# nxtMini.net
KiCad netlist of a schematic drawn in EAGLE
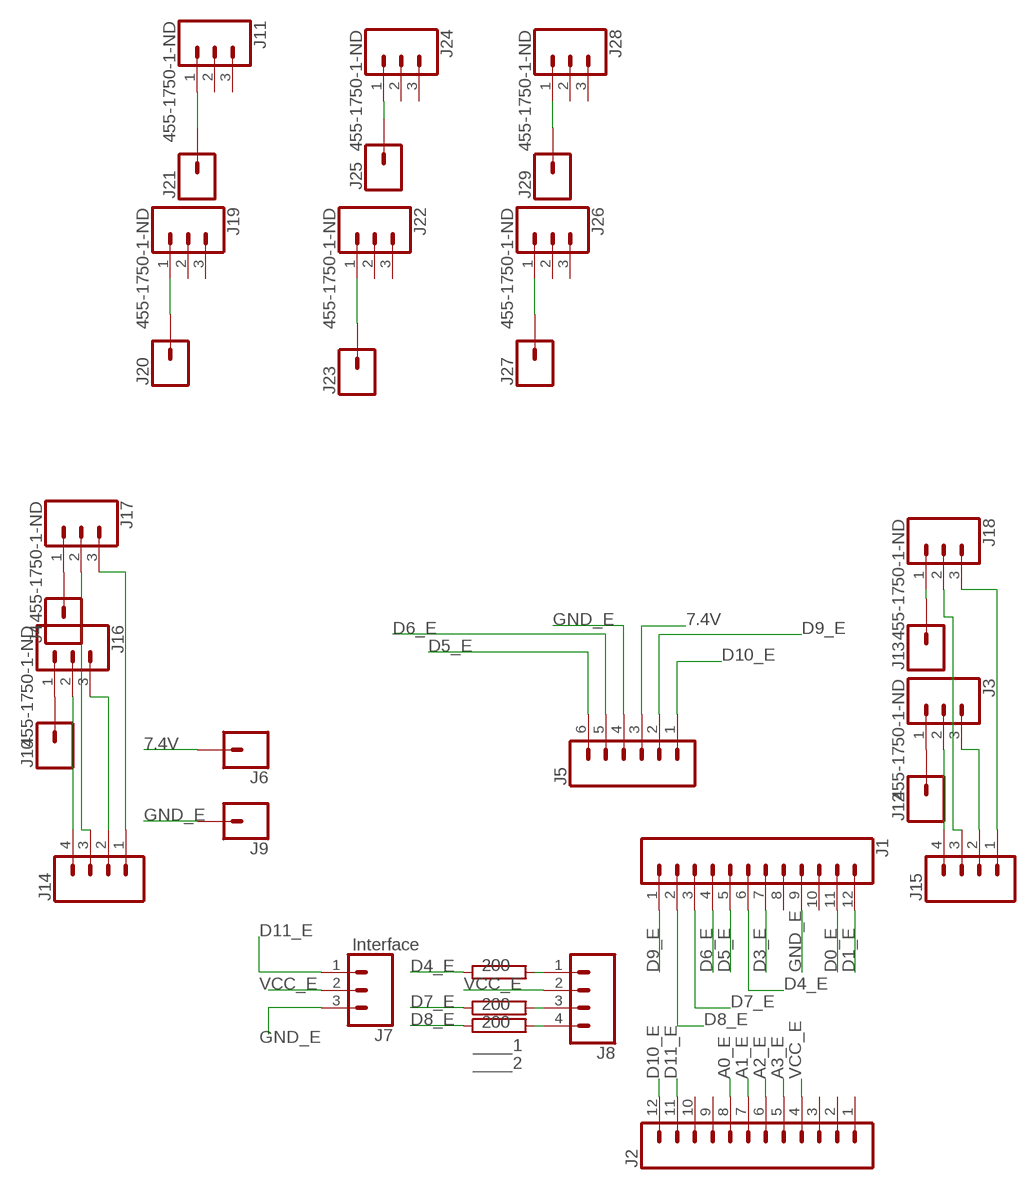
[diagram p0: schematic, sheet 1]

(export (version "E")
  (design (tool "Eeschema 10.0.6"))
  (components
    (comp (ref "200")
      (value "RCA0001")
      (footprint "eagle-import:CA0001")
      (libsource (lib "eagle-import") (part "RCA0001"))
    )
    (comp (ref "J1")
      (value "CONN_12")
      (footprint "eagle-import:1X12")
      (libsource (lib "eagle-import") (part "CONN_12"))
    )
    (comp (ref "J2")
      (value "CONN_12")
      (footprint "eagle-import:1X12")
      (libsource (lib "eagle-import") (part "CONN_12"))
    )
    (comp (ref "J3")
      (value "455-1750-1-ND")
      (footprint "eagle-import:1X03")
      (libsource (lib "eagle-import") (part "CONN_03"))
    )
    (comp (ref "J4")
      (value "CONN_01")
      (footprint "eagle-import:1X01")
      (libsource (lib "eagle-import") (part "CONN_01"))
    )
    (comp (ref "J5")
      (value "CONN_06SILK_FEMALE_PTH")
      (footprint "eagle-import:1X06")
      (libsource (lib "eagle-import") (part "CONN_06SILK_FEMALE_PTH"))
    )
    (comp (ref "J6")
      (value "CONN_01")
      (footprint "eagle-import:1X01")
      (libsource (lib "eagle-import") (part "CONN_01"))
    )
    (comp (ref "J7")
      (value "Interface")
      (footprint "eagle-import:1X03")
      (libsource (lib "eagle-import") (part "CONN_03"))
    )
    (comp (ref "J8")
      (value "CONN_04")
      (footprint "eagle-import:1X04")
      (libsource (lib "eagle-import") (part "CONN_04"))
    )
    (comp (ref "J9")
      (value "CONN_01")
      (footprint "eagle-import:1X01")
      (libsource (lib "eagle-import") (part "CONN_01"))
    )
    (comp (ref "J10")
      (value "CONN_01")
      (footprint "eagle-import:1X01")
      (libsource (lib "eagle-import") (part "CONN_01"))
    )
    (comp (ref "J11")
      (value "455-1750-1-ND")
      (footprint "eagle-import:1X03")
      (libsource (lib "eagle-import") (part "CONN_03"))
    )
    (comp (ref "J12")
      (value "CONN_01")
      (footprint "eagle-import:1X01")
      (libsource (lib "eagle-import") (part "CONN_01"))
    )
    (comp (ref "J13")
      (value "CONN_01")
      (footprint "eagle-import:1X01")
      (libsource (lib "eagle-import") (part "CONN_01"))
    )
    (comp (ref "J14")
      (value "CONN_04")
      (footprint "eagle-import:1X04")
      (libsource (lib "eagle-import") (part "CONN_04"))
    )
    (comp (ref "J15")
      (value "CONN_04")
      (footprint "eagle-import:1X04")
      (libsource (lib "eagle-import") (part "CONN_04"))
    )
    (comp (ref "J16")
      (value "455-1750-1-ND")
      (footprint "eagle-import:1X03")
      (libsource (lib "eagle-import") (part "CONN_03"))
    )
    (comp (ref "J17")
      (value "455-1750-1-ND")
      (footprint "eagle-import:1X03")
      (libsource (lib "eagle-import") (part "CONN_03"))
    )
    (comp (ref "J18")
      (value "455-1750-1-ND")
      (footprint "eagle-import:1X03")
      (libsource (lib "eagle-import") (part "CONN_03"))
    )
    (comp (ref "J19")
      (value "455-1750-1-ND")
      (footprint "eagle-import:1X03")
      (libsource (lib "eagle-import") (part "CONN_03"))
    )
    (comp (ref "J20")
      (value "CONN_01")
      (footprint "eagle-import:1X01")
      (libsource (lib "eagle-import") (part "CONN_01"))
    )
    (comp (ref "J21")
      (value "CONN_01")
      (footprint "eagle-import:1X01")
      (libsource (lib "eagle-import") (part "CONN_01"))
    )
    (comp (ref "J22")
      (value "455-1750-1-ND")
      (footprint "eagle-import:1X03")
      (libsource (lib "eagle-import") (part "CONN_03"))
    )
    (comp (ref "J23")
      (value "CONN_01")
      (footprint "eagle-import:1X01")
      (libsource (lib "eagle-import") (part "CONN_01"))
    )
    (comp (ref "J24")
      (value "455-1750-1-ND")
      (footprint "eagle-import:1X03")
      (libsource (lib "eagle-import") (part "CONN_03"))
    )
    (comp (ref "J25")
      (value "CONN_01")
      (footprint "eagle-import:1X01")
      (libsource (lib "eagle-import") (part "CONN_01"))
    )
    (comp (ref "J26")
      (value "455-1750-1-ND")
      (footprint "eagle-import:1X03")
      (libsource (lib "eagle-import") (part "CONN_03"))
    )
    (comp (ref "J27")
      (value "CONN_01")
      (footprint "eagle-import:1X01")
      (libsource (lib "eagle-import") (part "CONN_01"))
    )
    (comp (ref "J28")
      (value "455-1750-1-ND")
      (footprint "eagle-import:1X03")
      (libsource (lib "eagle-import") (part "CONN_03"))
    )
    (comp (ref "J29")
      (value "CONN_01")
      (footprint "eagle-import:1X01")
      (libsource (lib "eagle-import") (part "CONN_01"))
    )
    (comp (ref "____1")
      (value "200")
      (footprint "eagle-import:CA0001")
      (libsource (lib "eagle-import") (part "RCA0001"))
    )
    (comp (ref "____2")
      (value "200")
      (footprint "eagle-import:CA0001")
      (libsource (lib "eagle-import") (part "RCA0001"))
    )
  )
  (nets
    (net (code "1") (name "/7.4V") (class "Default")
      (node (ref "J5") (pin "3") (pinfunction "3_3") (pintype "passive"))
      (node (ref "J6") (pin "1") (pinfunction "1_1") (pintype "passive"))
    )
    (net (code "2") (name "/A0_E") (class "Default")
      (node (ref "J2") (pin "8") (pinfunction "8_8") (pintype "passive"))
    )
    (net (code "3") (name "/A1_E") (class "Default")
      (node (ref "J2") (pin "7") (pinfunction "7_7") (pintype "passive"))
    )
    (net (code "4") (name "/A2_E") (class "Default")
      (node (ref "J2") (pin "6") (pinfunction "6_6") (pintype "passive"))
    )
    (net (code "5") (name "/A3_E") (class "Default")
      (node (ref "J2") (pin "5") (pinfunction "5_5") (pintype "passive"))
    )
    (net (code "6") (name "/D0_E") (class "Default")
      (node (ref "J1") (pin "11") (pinfunction "11_11") (pintype "passive"))
    )
    (net (code "7") (name "/D1_E") (class "Default")
      (node (ref "J1") (pin "12") (pinfunction "12_12") (pintype "passive"))
    )
    (net (code "8") (name "/D3_E") (class "Default")
      (node (ref "J1") (pin "7") (pinfunction "7_7") (pintype "passive"))
    )
    (net (code "9") (name "/D4_E") (class "Default")
      (node (ref "200") (pin "1") (pinfunction "1_1") (pintype "passive"))
      (node (ref "J1") (pin "6") (pinfunction "6_6") (pintype "passive"))
    )
    (net (code "10") (name "/D5_E") (class "Default")
      (node (ref "J1") (pin "5") (pinfunction "5_5") (pintype "passive"))
      (node (ref "J5") (pin "6") (pinfunction "6_6") (pintype "passive"))
    )
    (net (code "11") (name "/D6_E") (class "Default")
      (node (ref "J1") (pin "4") (pinfunction "4_4") (pintype "passive"))
      (node (ref "J5") (pin "5") (pinfunction "5_5") (pintype "passive"))
    )
    (net (code "12") (name "/D7_E") (class "Default")
      (node (ref "J1") (pin "3") (pinfunction "3_3") (pintype "passive"))
      (node (ref "____1") (pin "1") (pinfunction "1_1") (pintype "passive"))
    )
    (net (code "13") (name "/D8_E") (class "Default")
      (node (ref "J1") (pin "2") (pinfunction "2_2") (pintype "passive"))
      (node (ref "____2") (pin "1") (pinfunction "1_1") (pintype "passive"))
    )
    (net (code "14") (name "/D9_E") (class "Default")
      (node (ref "J1") (pin "1") (pinfunction "1_1") (pintype "passive"))
      (node (ref "J5") (pin "2") (pinfunction "2_2") (pintype "passive"))
    )
    (net (code "15") (name "/D10_E") (class "Default")
      (node (ref "J2") (pin "12") (pinfunction "12_12") (pintype "passive"))
      (node (ref "J5") (pin "1") (pinfunction "1_1") (pintype "passive"))
    )
    (net (code "16") (name "/D11_E") (class "Default")
      (node (ref "J2") (pin "11") (pinfunction "11_11") (pintype "passive"))
      (node (ref "J7") (pin "1") (pinfunction "1_1") (pintype "passive"))
    )
    (net (code "17") (name "/GND_E") (class "Default")
      (node (ref "J1") (pin "9") (pinfunction "9_9") (pintype "passive"))
      (node (ref "J5") (pin "4") (pinfunction "4_4") (pintype "passive"))
      (node (ref "J7") (pin "3") (pinfunction "3_3") (pintype "passive"))
      (node (ref "J9") (pin "1") (pinfunction "1_1") (pintype "passive"))
    )
    (net (code "18") (name "/VCC_E") (class "Default")
      (node (ref "J2") (pin "4") (pinfunction "4_4") (pintype "passive"))
      (node (ref "J7") (pin "2") (pinfunction "2_2") (pintype "passive"))
      (node (ref "J8") (pin "2") (pinfunction "2_2") (pintype "passive"))
    )
    (net (code "19") (name "Net-(200-Pad2)") (class "Default")
      (node (ref "200") (pin "2") (pinfunction "2_2") (pintype "passive"))
      (node (ref "J8") (pin "1") (pinfunction "1_1") (pintype "passive"))
    )
    (net (code "20") (name "Net-(J8-Pad3)") (class "Default")
      (node (ref "J8") (pin "3") (pinfunction "3_3") (pintype "passive"))
      (node (ref "____1") (pin "2") (pinfunction "2_2") (pintype "passive"))
    )
    (net (code "21") (name "Net-(J8-Pad4)") (class "Default")
      (node (ref "J8") (pin "4") (pinfunction "4_4") (pintype "passive"))
      (node (ref "____2") (pin "2") (pinfunction "2_2") (pintype "passive"))
    )
    (net (code "22") (name "Net-(J10-Pad1)") (class "Default")
      (node (ref "J10") (pin "1") (pinfunction "1_1") (pintype "passive"))
      (node (ref "J16") (pin "1") (pinfunction "1_1") (pintype "passive"))
    )
    (net (code "23") (name "Net-(J11-Pad1)") (class "Default")
      (node (ref "J11") (pin "1") (pinfunction "1_1") (pintype "passive"))
      (node (ref "J21") (pin "1") (pinfunction "1_1") (pintype "passive"))
    )
    (net (code "24") (name "Net-(J12-Pad1)") (class "Default")
      (node (ref "J12") (pin "1") (pinfunction "1_1") (pintype "passive"))
      (node (ref "J3") (pin "1") (pinfunction "1_1") (pintype "passive"))
    )
    (net (code "25") (name "Net-(J13-Pad1)") (class "Default")
      (node (ref "J13") (pin "1") (pinfunction "1_1") (pintype "passive"))
      (node (ref "J18") (pin "1") (pinfunction "1_1") (pintype "passive"))
    )
    (net (code "26") (name "Net-(J14-Pad1)") (class "Default")
      (node (ref "J14") (pin "1") (pinfunction "1_1") (pintype "passive"))
      (node (ref "J17") (pin "3") (pinfunction "3_3") (pintype "passive"))
    )
    (net (code "27") (name "Net-(J14-Pad2)") (class "Default")
      (node (ref "J14") (pin "2") (pinfunction "2_2") (pintype "passive"))
      (node (ref "J16") (pin "3") (pinfunction "3_3") (pintype "passive"))
    )
    (net (code "28") (name "Net-(J14-Pad3)") (class "Default")
      (node (ref "J14") (pin "3") (pinfunction "3_3") (pintype "passive"))
      (node (ref "J17") (pin "2") (pinfunction "2_2") (pintype "passive"))
    )
    (net (code "29") (name "Net-(J14-Pad4)") (class "Default")
      (node (ref "J14") (pin "4") (pinfunction "4_4") (pintype "passive"))
      (node (ref "J16") (pin "2") (pinfunction "2_2") (pintype "passive"))
    )
    (net (code "30") (name "Net-(J15-Pad1)") (class "Default")
      (node (ref "J15") (pin "1") (pinfunction "1_1") (pintype "passive"))
      (node (ref "J18") (pin "3") (pinfunction "3_3") (pintype "passive"))
    )
    (net (code "31") (name "Net-(J15-Pad2)") (class "Default")
      (node (ref "J15") (pin "2") (pinfunction "2_2") (pintype "passive"))
      (node (ref "J3") (pin "3") (pinfunction "3_3") (pintype "passive"))
    )
    (net (code "32") (name "Net-(J15-Pad3)") (class "Default")
      (node (ref "J15") (pin "3") (pinfunction "3_3") (pintype "passive"))
      (node (ref "J18") (pin "2") (pinfunction "2_2") (pintype "passive"))
    )
    (net (code "33") (name "Net-(J15-Pad4)") (class "Default")
      (node (ref "J15") (pin "4") (pinfunction "4_4") (pintype "passive"))
      (node (ref "J3") (pin "2") (pinfunction "2_2") (pintype "passive"))
    )
    (net (code "34") (name "Net-(J17-Pad1)") (class "Default")
      (node (ref "J17") (pin "1") (pinfunction "1_1") (pintype "passive"))
      (node (ref "J4") (pin "1") (pinfunction "1_1") (pintype "passive"))
    )
    (net (code "35") (name "Net-(J19-Pad1)") (class "Default")
      (node (ref "J19") (pin "1") (pinfunction "1_1") (pintype "passive"))
      (node (ref "J20") (pin "1") (pinfunction "1_1") (pintype "passive"))
    )
    (net (code "36") (name "Net-(J22-Pad1)") (class "Default")
      (node (ref "J22") (pin "1") (pinfunction "1_1") (pintype "passive"))
      (node (ref "J23") (pin "1") (pinfunction "1_1") (pintype "passive"))
    )
    (net (code "37") (name "Net-(J24-Pad1)") (class "Default")
      (node (ref "J24") (pin "1") (pinfunction "1_1") (pintype "passive"))
      (node (ref "J25") (pin "1") (pinfunction "1_1") (pintype "passive"))
    )
    (net (code "38") (name "Net-(J26-Pad1)") (class "Default")
      (node (ref "J26") (pin "1") (pinfunction "1_1") (pintype "passive"))
      (node (ref "J27") (pin "1") (pinfunction "1_1") (pintype "passive"))
    )
    (net (code "39") (name "Net-(J28-Pad1)") (class "Default")
      (node (ref "J28") (pin "1") (pinfunction "1_1") (pintype "passive"))
      (node (ref "J29") (pin "1") (pinfunction "1_1") (pintype "passive"))
    )
    (net (code "40") (name "unconnected-(J1-Pad8)") (class "Default")
      (node (ref "J1") (pin "8") (pinfunction "8_8") (pintype "passive"))
    )
    (net (code "41") (name "unconnected-(J1-Pad10)") (class "Default")
      (node (ref "J1") (pin "10") (pinfunction "10_10") (pintype "passive"))
    )
    (net (code "42") (name "unconnected-(J2-Pad1)") (class "Default")
      (node (ref "J2") (pin "1") (pinfunction "1_1") (pintype "passive"))
    )
    (net (code "43") (name "unconnected-(J2-Pad2)") (class "Default")
      (node (ref "J2") (pin "2") (pinfunction "2_2") (pintype "passive"))
    )
    (net (code "44") (name "unconnected-(J2-Pad3)") (class "Default")
      (node (ref "J2") (pin "3") (pinfunction "3_3") (pintype "passive"))
    )
    (net (code "45") (name "unconnected-(J2-Pad9)") (class "Default")
      (node (ref "J2") (pin "9") (pinfunction "9_9") (pintype "passive"))
    )
    (net (code "46") (name "unconnected-(J2-Pad10)") (class "Default")
      (node (ref "J2") (pin "10") (pinfunction "10_10") (pintype "passive"))
    )
    (net (code "47") (name "unconnected-(J11-Pad2)") (class "Default")
      (node (ref "J11") (pin "2") (pinfunction "2_2") (pintype "passive"))
    )
    (net (code "48") (name "unconnected-(J11-Pad3)") (class "Default")
      (node (ref "J11") (pin "3") (pinfunction "3_3") (pintype "passive"))
    )
    (net (code "49") (name "unconnected-(J19-Pad2)") (class "Default")
      (node (ref "J19") (pin "2") (pinfunction "2_2") (pintype "passive"))
    )
    (net (code "50") (name "unconnected-(J19-Pad3)") (class "Default")
      (node (ref "J19") (pin "3") (pinfunction "3_3") (pintype "passive"))
    )
    (net (code "51") (name "unconnected-(J22-Pad2)") (class "Default")
      (node (ref "J22") (pin "2") (pinfunction "2_2") (pintype "passive"))
    )
    (net (code "52") (name "unconnected-(J22-Pad3)") (class "Default")
      (node (ref "J22") (pin "3") (pinfunction "3_3") (pintype "passive"))
    )
    (net (code "53") (name "unconnected-(J24-Pad2)") (class "Default")
      (node (ref "J24") (pin "2") (pinfunction "2_2") (pintype "passive"))
    )
    (net (code "54") (name "unconnected-(J24-Pad3)") (class "Default")
      (node (ref "J24") (pin "3") (pinfunction "3_3") (pintype "passive"))
    )
    (net (code "55") (name "unconnected-(J26-Pad2)") (class "Default")
      (node (ref "J26") (pin "2") (pinfunction "2_2") (pintype "passive"))
    )
    (net (code "56") (name "unconnected-(J26-Pad3)") (class "Default")
      (node (ref "J26") (pin "3") (pinfunction "3_3") (pintype "passive"))
    )
    (net (code "57") (name "unconnected-(J28-Pad2)") (class "Default")
      (node (ref "J28") (pin "2") (pinfunction "2_2") (pintype "passive"))
    )
    (net (code "58") (name "unconnected-(J28-Pad3)") (class "Default")
      (node (ref "J28") (pin "3") (pinfunction "3_3") (pintype "passive"))
    )
  )
)
